# Orthrus_3_0_1-eagle_7_6.net
KiCad netlist of a schematic drawn in EAGLE
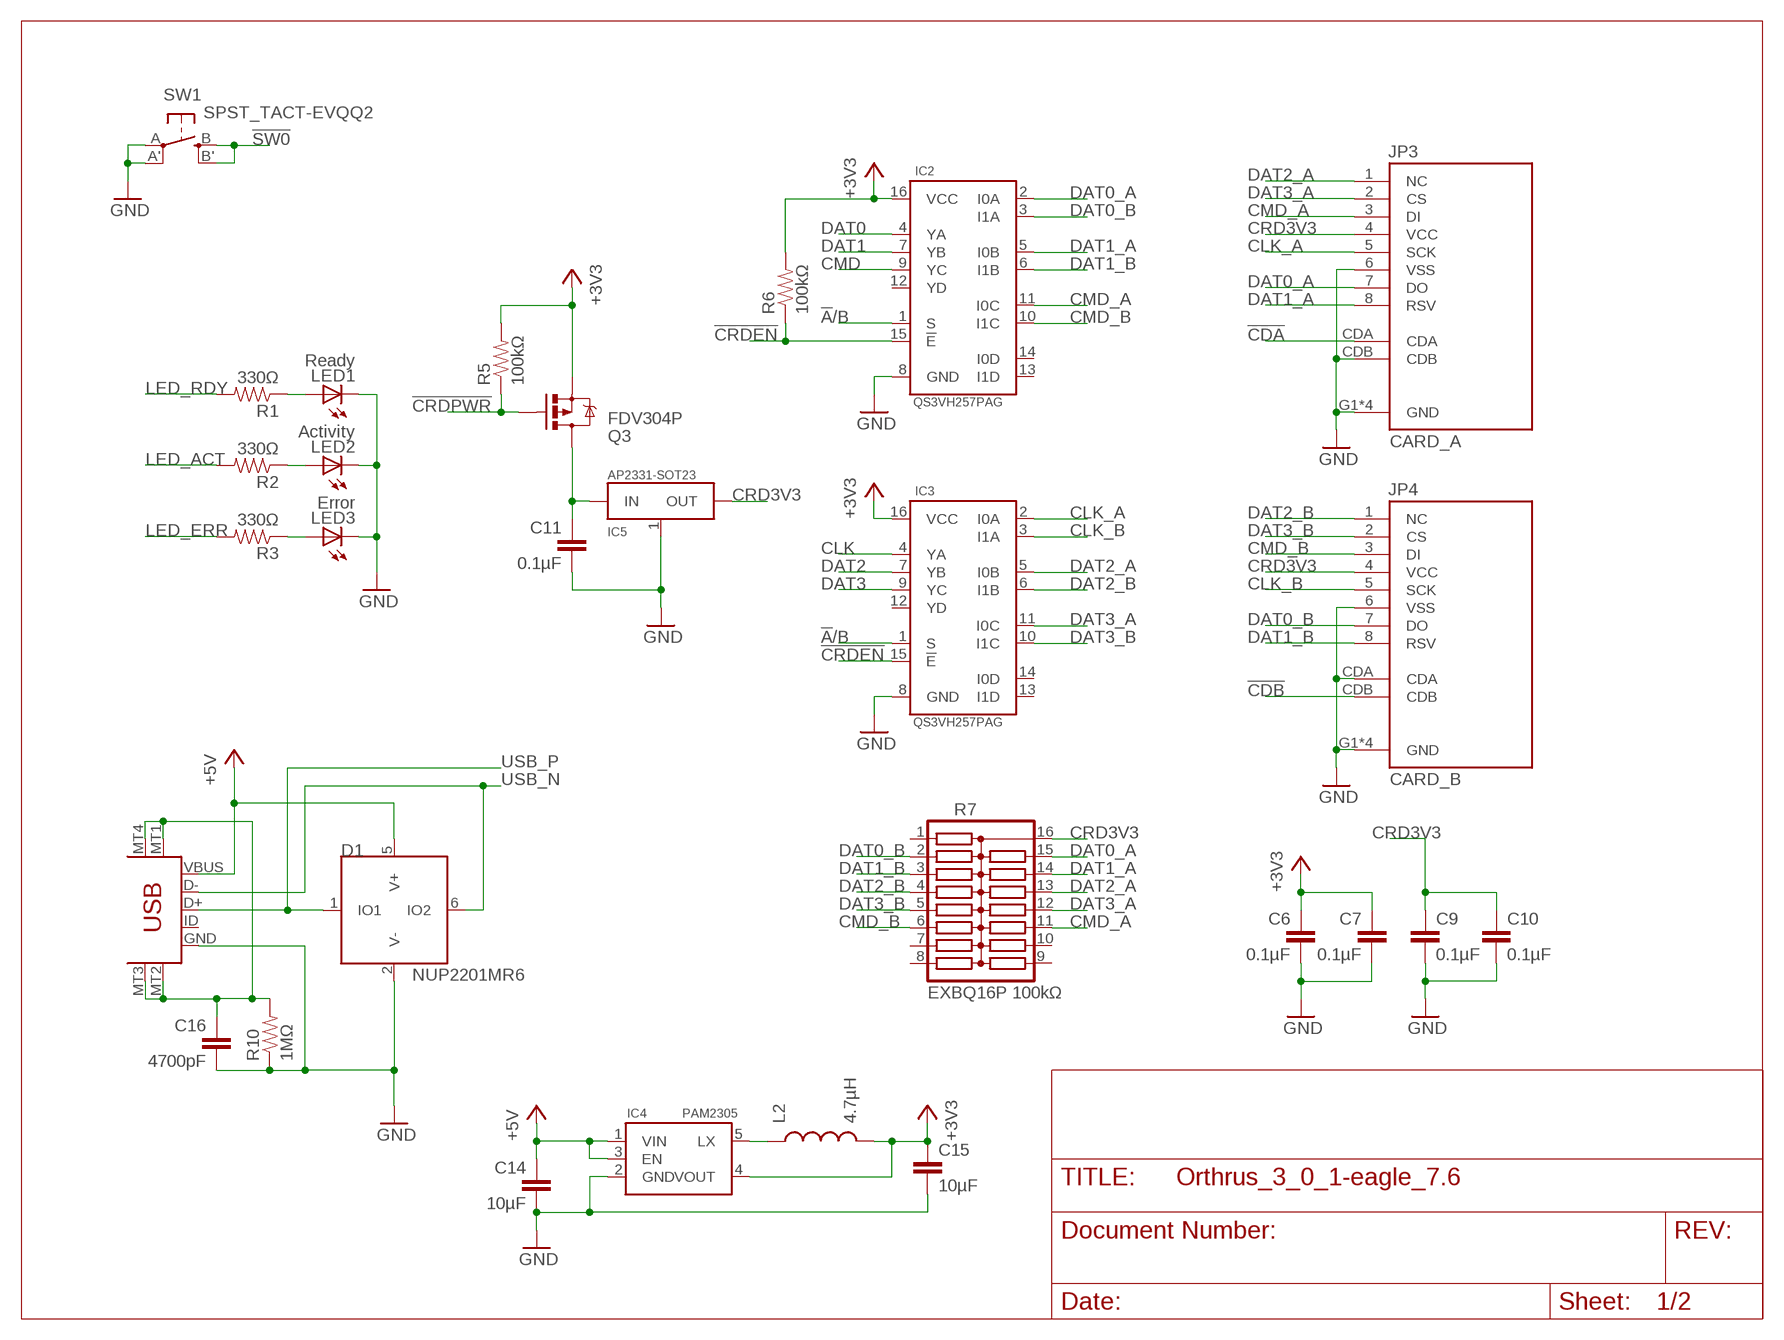
[diagram p0: schematic, sheet 1]
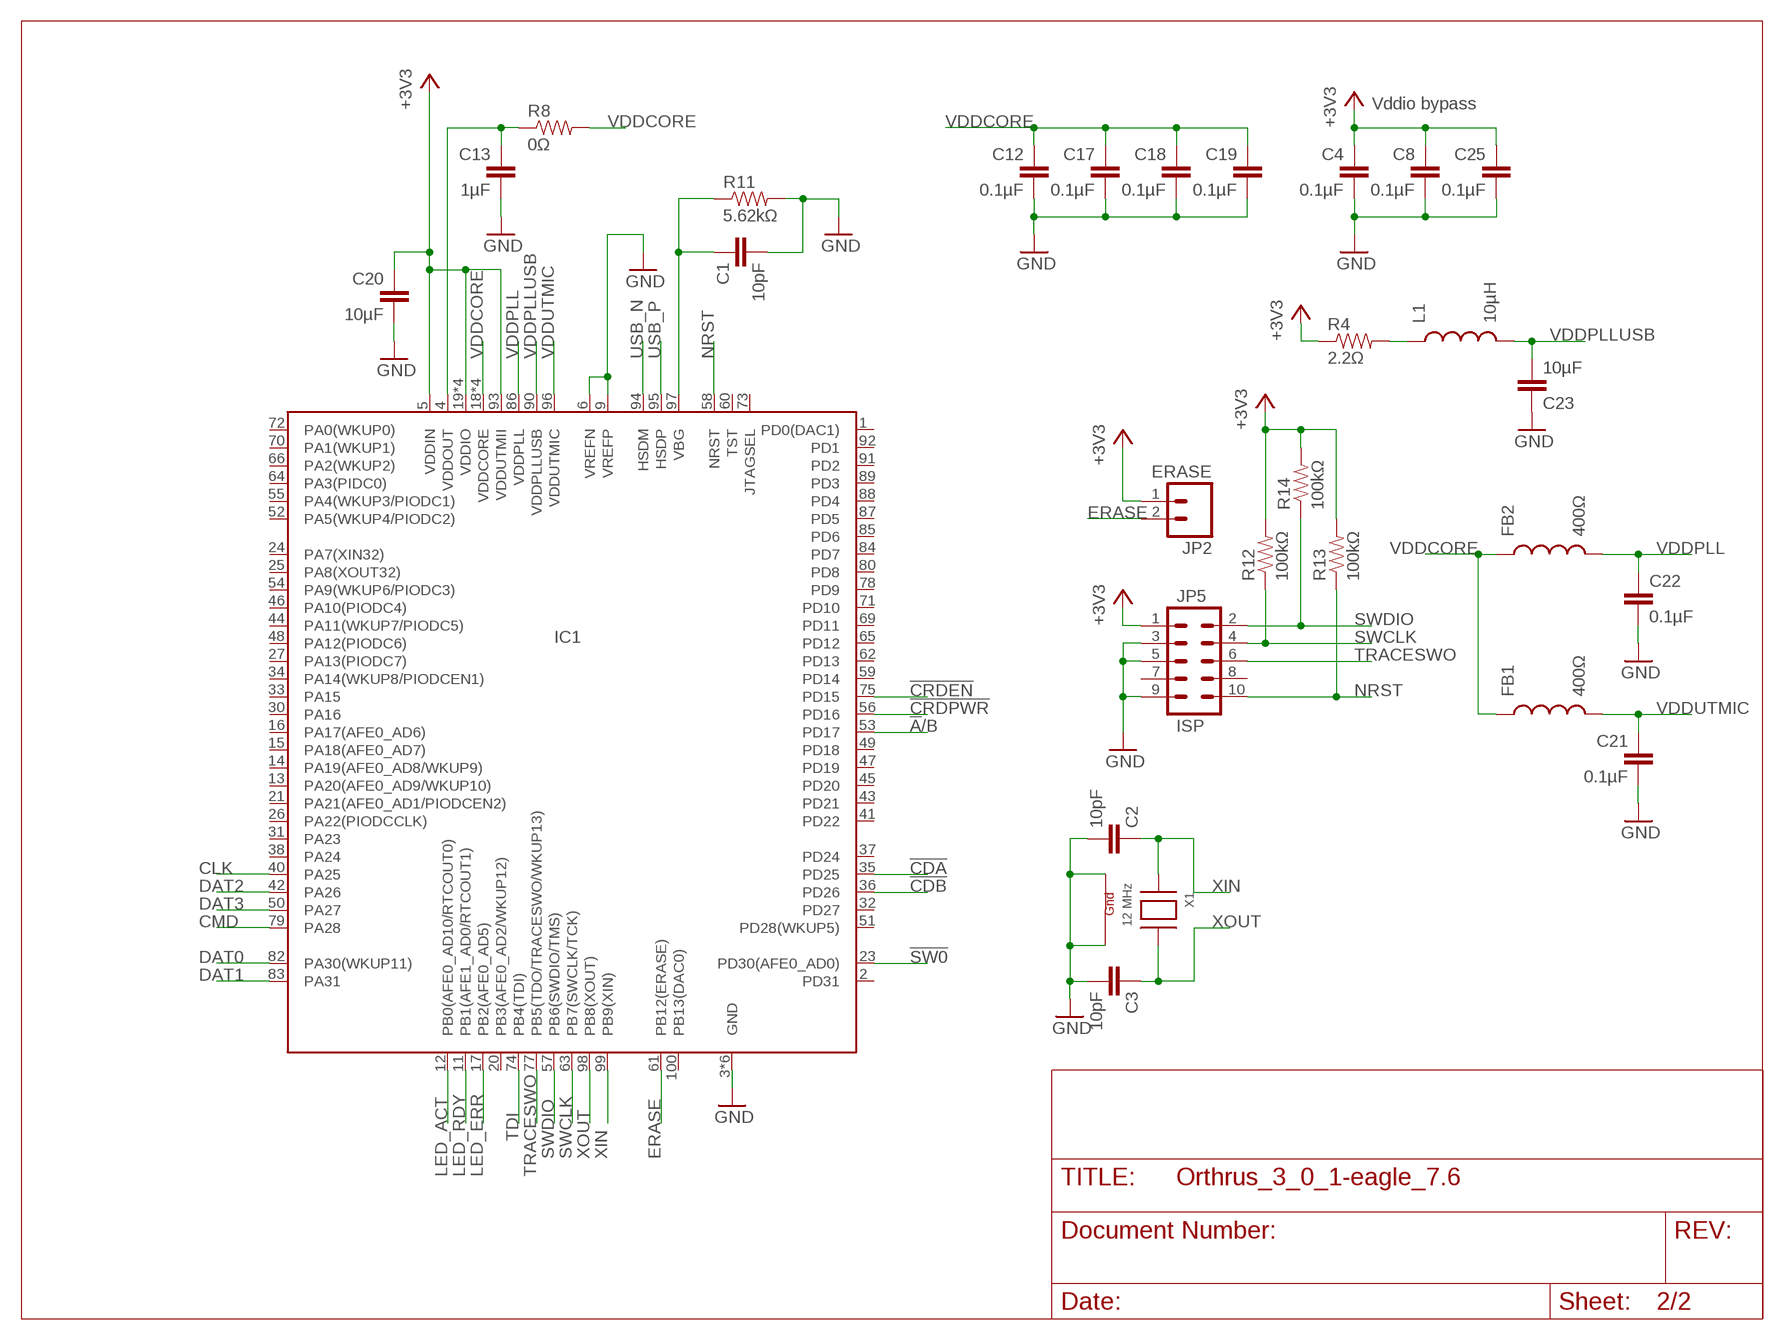
[diagram p1: schematic, sheet 2]

(export (version "E")
  (design (tool "Eeschema 10.0.6"))
  (components
    (comp (ref "C6")
      (value "0.1µF")
      (footprint "eagle-import:0805")
      (libsource (lib "eagle-import") (part "CAP0805"))
    )
    (comp (ref "C7")
      (value "0.1µF")
      (footprint "eagle-import:0805")
      (libsource (lib "eagle-import") (part "CAP0805"))
    )
    (comp (ref "C9")
      (value "0.1µF")
      (footprint "eagle-import:0805")
      (libsource (lib "eagle-import") (part "CAP0805"))
    )
    (comp (ref "C10")
      (value "0.1µF")
      (footprint "eagle-import:0805")
      (libsource (lib "eagle-import") (part "CAP0805"))
    )
    (comp (ref "C11")
      (value "0.1µF")
      (footprint "eagle-import:0805")
      (libsource (lib "eagle-import") (part "CAP0805"))
    )
    (comp (ref "C14")
      (value "10µF")
      (footprint "eagle-import:0805")
      (libsource (lib "eagle-import") (part "CAP0805"))
    )
    (comp (ref "C15")
      (value "10µF")
      (footprint "eagle-import:0805")
      (libsource (lib "eagle-import") (part "CAP0805"))
    )
    (comp (ref "C16")
      (value "4700pF")
      (footprint "eagle-import:0805")
      (libsource (lib "eagle-import") (part "CAP0805"))
    )
    (comp (ref "D1")
      (value "NUP2201MR6")
      (footprint "eagle-import:SOT23-6")
      (libsource (lib "eagle-import") (part "NUP2201MR6"))
    )
    (comp (ref "IC2")
      (value "QS3VH257PAG")
      (footprint "eagle-import:TSSOP16")
      (libsource (lib "eagle-import") (part "QS3VH257PAG"))
    )
    (comp (ref "IC3")
      (value "QS3VH257PAG")
      (footprint "eagle-import:TSSOP16")
      (libsource (lib "eagle-import") (part "QS3VH257PAG"))
    )
    (comp (ref "IC4")
      (value "PAM2305")
      (footprint "eagle-import:SOT23-5")
      (libsource (lib "eagle-import") (part "SC189XSKTRTSC189XSKTRT"))
    )
    (comp (ref "IC5")
      (value "AP2331-SOT23")
      (footprint "eagle-import:SOT23-3")
      (libsource (lib "eagle-import") (part "AP2331-SOT23"))
    )
    (comp (ref "JP1")
      (value "USB-5PIN-MICROB")
      (footprint "eagle-import:USB-MICROB")
      (libsource (lib "eagle-import") (part "USB-5PIN-MICROB"))
    )
    (comp (ref "JP3")
      (value "CARD_A")
      (footprint "eagle-import:DM3D-SF")
      (libsource (lib "eagle-import") (part "DM3D-SF"))
    )
    (comp (ref "JP4")
      (value "CARD_B")
      (footprint "eagle-import:DM3D-SF")
      (libsource (lib "eagle-import") (part "DM3D-SF"))
    )
    (comp (ref "L2")
      (value "4.7µH")
      (footprint "eagle-import:0805")
      (libsource (lib "eagle-import") (part "INDUCTOR0805"))
    )
    (comp (ref "LED1")
      (value "Ready")
      (footprint "eagle-import:CHIP-LED0805")
      (libsource (lib "eagle-import") (part "LEDCHIP-LED0805"))
    )
    (comp (ref "LED2")
      (value "Activity")
      (footprint "eagle-import:CHIP-LED0805")
      (libsource (lib "eagle-import") (part "LEDCHIP-LED0805"))
    )
    (comp (ref "LED3")
      (value "Error")
      (footprint "eagle-import:CHIP-LED0805")
      (libsource (lib "eagle-import") (part "LEDCHIP-LED0805"))
    )
    (comp (ref "Q3")
      (value "FDV304P")
      (footprint "eagle-import:SOT23-3")
      (libsource (lib "eagle-import") (part "MOSFET-PCHANNELSMD"))
    )
    (comp (ref "R1")
      (value "330Ω")
      (footprint "eagle-import:0805")
      (libsource (lib "eagle-import") (part "RESISTOR0805-RES"))
    )
    (comp (ref "R2")
      (value "330Ω")
      (footprint "eagle-import:0805")
      (libsource (lib "eagle-import") (part "RESISTOR0805-RES"))
    )
    (comp (ref "R3")
      (value "330Ω")
      (footprint "eagle-import:0805")
      (libsource (lib "eagle-import") (part "RESISTOR0805-RES"))
    )
    (comp (ref "R5")
      (value "100kΩ")
      (footprint "eagle-import:0805")
      (libsource (lib "eagle-import") (part "RESISTOR0805-RES"))
    )
    (comp (ref "R6")
      (value "100kΩ")
      (footprint "eagle-import:0805")
      (libsource (lib "eagle-import") (part "RESISTOR0805-RES"))
    )
    (comp (ref "R7")
      (value "EXBQ16P 100kΩ")
      (footprint "eagle-import:4816P")
      (fields (field (name "MF") "BOURNS, INC.") (field (name "MPN") "4816P-T02-824LF"))
      (libsource (lib "eagle-import") (part "4816P-T02"))
    )
    (comp (ref "R10")
      (value "1MΩ")
      (footprint "eagle-import:0805")
      (libsource (lib "eagle-import") (part "RESISTOR0805-RES"))
    )
    (comp (ref "SW1")
      (value "SPST_TACT-EVQQ2")
      (footprint "eagle-import:EVQ-Q2")
      (libsource (lib "eagle-import") (part "SPST_TACT-EVQQ2"))
    )
    (comp (ref "C1")
      (value "10pF")
      (footprint "eagle-import:0805")
      (libsource (lib "eagle-import") (part "CAP0805"))
    )
    (comp (ref "C2")
      (value "10pF")
      (footprint "eagle-import:0805")
      (libsource (lib "eagle-import") (part "CAP0805"))
    )
    (comp (ref "C3")
      (value "10pF")
      (footprint "eagle-import:0805")
      (libsource (lib "eagle-import") (part "CAP0805"))
    )
    (comp (ref "C4")
      (value "0.1µF")
      (footprint "eagle-import:0805")
      (libsource (lib "eagle-import") (part "CAP0805"))
    )
    (comp (ref "C8")
      (value "0.1µF")
      (footprint "eagle-import:0805")
      (libsource (lib "eagle-import") (part "CAP0805"))
    )
    (comp (ref "C12")
      (value "0.1µF")
      (footprint "eagle-import:0805")
      (libsource (lib "eagle-import") (part "CAP0805"))
    )
    (comp (ref "C13")
      (value "1µF")
      (footprint "eagle-import:0805")
      (libsource (lib "eagle-import") (part "CAP0805"))
    )
    (comp (ref "C17")
      (value "0.1µF")
      (footprint "eagle-import:0805")
      (libsource (lib "eagle-import") (part "CAP0805"))
    )
    (comp (ref "C18")
      (value "0.1µF")
      (footprint "eagle-import:0805")
      (libsource (lib "eagle-import") (part "CAP0805"))
    )
    (comp (ref "C19")
      (value "0.1µF")
      (footprint "eagle-import:0805")
      (libsource (lib "eagle-import") (part "CAP0805"))
    )
    (comp (ref "C20")
      (value "10µF")
      (footprint "eagle-import:0805")
      (libsource (lib "eagle-import") (part "CAP0805"))
    )
    (comp (ref "C21")
      (value "0.1µF")
      (footprint "eagle-import:0805")
      (libsource (lib "eagle-import") (part "CAP0805"))
    )
    (comp (ref "C22")
      (value "0.1µF")
      (footprint "eagle-import:0805")
      (libsource (lib "eagle-import") (part "CAP0805"))
    )
    (comp (ref "C23")
      (value "10µF")
      (footprint "eagle-import:0805")
      (libsource (lib "eagle-import") (part "CAP0805"))
    )
    (comp (ref "C25")
      (value "0.1µF")
      (footprint "eagle-import:0805")
      (libsource (lib "eagle-import") (part "CAP0805"))
    )
    (comp (ref "FB1")
      (value "400Ω")
      (footprint "eagle-import:0805")
      (libsource (lib "eagle-import") (part "INDUCTOR0805"))
    )
    (comp (ref "FB2")
      (value "400Ω")
      (footprint "eagle-import:0805")
      (libsource (lib "eagle-import") (part "INDUCTOR0805"))
    )
    (comp (ref "IC1")
      (value "ATSAMS70NXXAN")
      (footprint "eagle-import:TQFP100")
      (libsource (lib "eagle-import") (part "ATSAMS70NXXAN"))
    )
    (comp (ref "JP2")
      (value "ERASE")
      (footprint "eagle-import:1X02")
      (libsource (lib "eagle-import") (part "M02PTH"))
    )
    (comp (ref "JP5")
      (value "ISP")
      (footprint "eagle-import:JTAGICE3-50MIL")
      (libsource (lib "eagle-import") (part "M05X250MIL"))
    )
    (comp (ref "L1")
      (value "10µH")
      (footprint "eagle-import:0805")
      (libsource (lib "eagle-import") (part "INDUCTOR0805"))
    )
    (comp (ref "R4")
      (value "2.2Ω")
      (footprint "eagle-import:0805")
      (libsource (lib "eagle-import") (part "RESISTOR0805-RES"))
    )
    (comp (ref "R8")
      (value "0Ω")
      (footprint "eagle-import:0805-WITH-JUMPER")
      (libsource (lib "eagle-import") (part "RESISTOR0805-WITH-JUMPER"))
    )
    (comp (ref "R11")
      (value "5.62kΩ")
      (footprint "eagle-import:0805")
      (libsource (lib "eagle-import") (part "RESISTOR0805-RES"))
    )
    (comp (ref "R12")
      (value "100kΩ")
      (footprint "eagle-import:0805")
      (libsource (lib "eagle-import") (part "RESISTOR0805-RES"))
    )
    (comp (ref "R13")
      (value "100kΩ")
      (footprint "eagle-import:0805")
      (libsource (lib "eagle-import") (part "RESISTOR0805-RES"))
    )
    (comp (ref "R14")
      (value "100kΩ")
      (footprint "eagle-import:0805")
      (libsource (lib "eagle-import") (part "RESISTOR0805-RES"))
    )
    (comp (ref "X1")
      (value "12 MHz")
      (footprint "eagle-import:NX3225")
      (libsource (lib "eagle-import") (part "XTAL-4-3225"))
    )
  )
  (nets
    (net (code "1") (name "+3V3") (class "Default")
      (node (ref "C15") (pin "1") (pinfunction "1_1") (pintype "passive"))
      (node (ref "C20") (pin "1") (pinfunction "1_1") (pintype "passive"))
      (node (ref "C25") (pin "1") (pinfunction "1_1") (pintype "passive"))
      (node (ref "C4") (pin "1") (pinfunction "1_1") (pintype "passive"))
      (node (ref "C6") (pin "1") (pinfunction "1_1") (pintype "passive"))
      (node (ref "C7") (pin "1") (pinfunction "1_1") (pintype "passive"))
      (node (ref "C8") (pin "1") (pinfunction "1_1") (pintype "passive"))
      (node (ref "IC1") (pin "19") (pinfunction "VDDIO_19") (pintype "bidirectional"))
      (node (ref "IC1") (pin "28") (pinfunction "VDDIO_28") (pintype "bidirectional"))
      (node (ref "IC1") (pin "5") (pinfunction "VDDIN_5") (pintype "bidirectional"))
      (node (ref "IC1") (pin "68") (pinfunction "VDDIO_68") (pintype "bidirectional"))
      (node (ref "IC1") (pin "81") (pinfunction "VDDIO_81") (pintype "bidirectional"))
      (node (ref "IC1") (pin "93") (pinfunction "VDDUTMII_93") (pintype "bidirectional"))
      (node (ref "IC2") (pin "16") (pinfunction "VCC_16") (pintype "power_in"))
      (node (ref "IC3") (pin "16") (pinfunction "VCC_16") (pintype "power_in"))
      (node (ref "IC4") (pin "4") (pinfunction "VOUT_4") (pintype "bidirectional"))
      (node (ref "JP2") (pin "1") (pinfunction "1_1") (pintype "passive"))
      (node (ref "JP5") (pin "1") (pinfunction "1_1") (pintype "passive"))
      (node (ref "L2") (pin "2") (pinfunction "2_2") (pintype "passive"))
      (node (ref "Q3") (pin "2") (pinfunction "S_2") (pintype "passive"))
      (node (ref "R12") (pin "2") (pinfunction "2_2") (pintype "passive"))
      (node (ref "R13") (pin "2") (pinfunction "2_2") (pintype "passive"))
      (node (ref "R14") (pin "2") (pinfunction "2_2") (pintype "passive"))
      (node (ref "R4") (pin "1") (pinfunction "1_1") (pintype "passive"))
      (node (ref "R5") (pin "2") (pinfunction "2_2") (pintype "passive"))
      (node (ref "R6") (pin "2") (pinfunction "2_2") (pintype "passive"))
    )
    (net (code "2") (name "+5V") (class "Default")
      (node (ref "C14") (pin "1") (pinfunction "1_1") (pintype "passive"))
      (node (ref "D1") (pin "5") (pinfunction "V+_5") (pintype "bidirectional"))
      (node (ref "IC4") (pin "1") (pinfunction "VIN_1") (pintype "bidirectional"))
      (node (ref "IC4") (pin "3") (pinfunction "EN_3") (pintype "bidirectional"))
      (node (ref "JP1") (pin "VBUS") (pinfunction "VBUS_VBUS") (pintype "bidirectional"))
    )
    (net (code "3") (name "CLK") (class "Default")
      (node (ref "IC1") (pin "40") (pinfunction "PA25_40") (pintype "bidirectional"))
      (node (ref "IC3") (pin "4") (pinfunction "YA_4") (pintype "bidirectional"))
    )
    (net (code "4") (name "CLK_A") (class "Default")
      (node (ref "IC3") (pin "2") (pinfunction "I0A_2") (pintype "bidirectional"))
      (node (ref "JP3") (pin "5") (pinfunction "SCK_5") (pintype "bidirectional"))
    )
    (net (code "5") (name "CLK_B") (class "Default")
      (node (ref "IC3") (pin "3") (pinfunction "I1A_3") (pintype "bidirectional"))
      (node (ref "JP4") (pin "5") (pinfunction "SCK_5") (pintype "bidirectional"))
    )
    (net (code "6") (name "CMD") (class "Default")
      (node (ref "IC1") (pin "79") (pinfunction "PA28_79") (pintype "bidirectional"))
      (node (ref "IC2") (pin "9") (pinfunction "YC_9") (pintype "bidirectional"))
    )
    (net (code "7") (name "CMD_A") (class "Default")
      (node (ref "IC2") (pin "11") (pinfunction "I0C_11") (pintype "bidirectional"))
      (node (ref "JP3") (pin "3") (pinfunction "DI_3") (pintype "bidirectional"))
      (node (ref "R7") (pin "11") (pinfunction "11_11") (pintype "passive"))
    )
    (net (code "8") (name "CMD_B") (class "Default")
      (node (ref "IC2") (pin "10") (pinfunction "I1C_10") (pintype "bidirectional"))
      (node (ref "JP4") (pin "3") (pinfunction "DI_3") (pintype "bidirectional"))
      (node (ref "R7") (pin "6") (pinfunction "6_6") (pintype "passive"))
    )
    (net (code "9") (name "CRD3V3") (class "Default")
      (node (ref "C10") (pin "1") (pinfunction "1_1") (pintype "passive"))
      (node (ref "C9") (pin "1") (pinfunction "1_1") (pintype "passive"))
      (node (ref "IC5") (pin "2") (pinfunction "OUT_2") (pintype "output"))
      (node (ref "JP3") (pin "4") (pinfunction "VCC_4") (pintype "bidirectional"))
      (node (ref "JP4") (pin "4") (pinfunction "VCC_4") (pintype "bidirectional"))
      (node (ref "R7") (pin "16") (pinfunction "16_16") (pintype "passive"))
    )
    (net (code "10") (name "DAT0") (class "Default")
      (node (ref "IC1") (pin "82") (pinfunction "PA30(WKUP11)_82") (pintype "bidirectional"))
      (node (ref "IC2") (pin "4") (pinfunction "YA_4") (pintype "bidirectional"))
    )
    (net (code "11") (name "DAT0_A") (class "Default")
      (node (ref "IC2") (pin "2") (pinfunction "I0A_2") (pintype "bidirectional"))
      (node (ref "JP3") (pin "7") (pinfunction "DO_7") (pintype "bidirectional"))
      (node (ref "R7") (pin "15") (pinfunction "15_15") (pintype "passive"))
    )
    (net (code "12") (name "DAT0_B") (class "Default")
      (node (ref "IC2") (pin "3") (pinfunction "I1A_3") (pintype "bidirectional"))
      (node (ref "JP4") (pin "7") (pinfunction "DO_7") (pintype "bidirectional"))
      (node (ref "R7") (pin "2") (pinfunction "2_2") (pintype "passive"))
    )
    (net (code "13") (name "DAT1") (class "Default")
      (node (ref "IC1") (pin "83") (pinfunction "PA31_83") (pintype "bidirectional"))
      (node (ref "IC2") (pin "7") (pinfunction "YB_7") (pintype "bidirectional"))
    )
    (net (code "14") (name "DAT1_A") (class "Default")
      (node (ref "IC2") (pin "5") (pinfunction "I0B_5") (pintype "bidirectional"))
      (node (ref "JP3") (pin "8") (pinfunction "RSV_8") (pintype "bidirectional"))
      (node (ref "R7") (pin "14") (pinfunction "14_14") (pintype "passive"))
    )
    (net (code "15") (name "DAT1_B") (class "Default")
      (node (ref "IC2") (pin "6") (pinfunction "I1B_6") (pintype "bidirectional"))
      (node (ref "JP4") (pin "8") (pinfunction "RSV_8") (pintype "bidirectional"))
      (node (ref "R7") (pin "3") (pinfunction "3_3") (pintype "passive"))
    )
    (net (code "16") (name "DAT2") (class "Default")
      (node (ref "IC1") (pin "42") (pinfunction "PA26_42") (pintype "bidirectional"))
      (node (ref "IC3") (pin "7") (pinfunction "YB_7") (pintype "bidirectional"))
    )
    (net (code "17") (name "DAT2_A") (class "Default")
      (node (ref "IC3") (pin "5") (pinfunction "I0B_5") (pintype "bidirectional"))
      (node (ref "JP3") (pin "1") (pinfunction "NC_1") (pintype "bidirectional"))
      (node (ref "R7") (pin "13") (pinfunction "13_13") (pintype "passive"))
    )
    (net (code "18") (name "DAT2_B") (class "Default")
      (node (ref "IC3") (pin "6") (pinfunction "I1B_6") (pintype "bidirectional"))
      (node (ref "JP4") (pin "1") (pinfunction "NC_1") (pintype "bidirectional"))
      (node (ref "R7") (pin "4") (pinfunction "4_4") (pintype "passive"))
    )
    (net (code "19") (name "DAT3") (class "Default")
      (node (ref "IC1") (pin "50") (pinfunction "PA27_50") (pintype "bidirectional"))
      (node (ref "IC3") (pin "9") (pinfunction "YC_9") (pintype "bidirectional"))
    )
    (net (code "20") (name "DAT3_A") (class "Default")
      (node (ref "IC3") (pin "11") (pinfunction "I0C_11") (pintype "bidirectional"))
      (node (ref "JP3") (pin "2") (pinfunction "CS_2") (pintype "bidirectional"))
      (node (ref "R7") (pin "12") (pinfunction "12_12") (pintype "passive"))
    )
    (net (code "21") (name "DAT3_B") (class "Default")
      (node (ref "IC3") (pin "10") (pinfunction "I1C_10") (pintype "bidirectional"))
      (node (ref "JP4") (pin "2") (pinfunction "CS_2") (pintype "bidirectional"))
      (node (ref "R7") (pin "5") (pinfunction "5_5") (pintype "passive"))
    )
    (net (code "22") (name "ERASE") (class "Default")
      (node (ref "IC1") (pin "61") (pinfunction "PB12(ERASE)_61") (pintype "bidirectional"))
      (node (ref "JP2") (pin "2") (pinfunction "2_2") (pintype "passive"))
    )
    (net (code "23") (name "GND") (class "Default")
      (node (ref "C1") (pin "2") (pinfunction "2_2") (pintype "passive"))
      (node (ref "C10") (pin "2") (pinfunction "2_2") (pintype "passive"))
      (node (ref "C11") (pin "2") (pinfunction "2_2") (pintype "passive"))
      (node (ref "C12") (pin "2") (pinfunction "2_2") (pintype "passive"))
      (node (ref "C13") (pin "2") (pinfunction "2_2") (pintype "passive"))
      (node (ref "C14") (pin "2") (pinfunction "2_2") (pintype "passive"))
      (node (ref "C15") (pin "2") (pinfunction "2_2") (pintype "passive"))
      (node (ref "C16") (pin "2") (pinfunction "2_2") (pintype "passive"))
      (node (ref "C17") (pin "2") (pinfunction "2_2") (pintype "passive"))
      (node (ref "C18") (pin "2") (pinfunction "2_2") (pintype "passive"))
      (node (ref "C19") (pin "2") (pinfunction "2_2") (pintype "passive"))
      (node (ref "C2") (pin "2") (pinfunction "2_2") (pintype "passive"))
      (node (ref "C20") (pin "2") (pinfunction "2_2") (pintype "passive"))
      (node (ref "C21") (pin "2") (pinfunction "2_2") (pintype "passive"))
      (node (ref "C22") (pin "2") (pinfunction "2_2") (pintype "passive"))
      (node (ref "C23") (pin "1") (pinfunction "1_1") (pintype "passive"))
      (node (ref "C25") (pin "2") (pinfunction "2_2") (pintype "passive"))
      (node (ref "C3") (pin "2") (pinfunction "2_2") (pintype "passive"))
      (node (ref "C4") (pin "2") (pinfunction "2_2") (pintype "passive"))
      (node (ref "C6") (pin "2") (pinfunction "2_2") (pintype "passive"))
      (node (ref "C7") (pin "2") (pinfunction "2_2") (pintype "passive"))
      (node (ref "C8") (pin "2") (pinfunction "2_2") (pintype "passive"))
      (node (ref "C9") (pin "2") (pinfunction "2_2") (pintype "passive"))
      (node (ref "D1") (pin "2") (pinfunction "V-_2") (pintype "bidirectional"))
      (node (ref "IC1") (pin "10") (pinfunction "GND_10") (pintype "bidirectional"))
      (node (ref "IC1") (pin "29") (pinfunction "GND_29") (pintype "bidirectional"))
      (node (ref "IC1") (pin "3") (pinfunction "GND_3") (pintype "bidirectional"))
      (node (ref "IC1") (pin "6") (pinfunction "VREFN_6") (pintype "bidirectional"))
      (node (ref "IC1") (pin "67") (pinfunction "GND_67") (pintype "bidirectional"))
      (node (ref "IC1") (pin "7") (pinfunction "GND_7") (pintype "bidirectional"))
      (node (ref "IC1") (pin "8") (pinfunction "GND_8") (pintype "bidirectional"))
      (node (ref "IC1") (pin "9") (pinfunction "VREFP_9") (pintype "bidirectional"))
      (node (ref "IC2") (pin "8") (pinfunction "GND_8") (pintype "power_in"))
      (node (ref "IC3") (pin "8") (pinfunction "GND_8") (pintype "power_in"))
      (node (ref "IC4") (pin "2") (pinfunction "GND_2") (pintype "bidirectional"))
      (node (ref "IC5") (pin "1") (pinfunction "GND_1") (pintype "power_in"))
      (node (ref "JP1") (pin "GND") (pinfunction "GND_GND") (pintype "bidirectional"))
      (node (ref "JP3") (pin "6") (pinfunction "VSS_6") (pintype "bidirectional"))
      (node (ref "JP3") (pin "CDB") (pinfunction "CDB_CDB") (pintype "bidirectional"))
      (node (ref "JP3") (pin "G1") (pinfunction "GND_G1") (pintype "bidirectional"))
      (node (ref "JP3") (pin "G2") (pinfunction "GND_G2") (pintype "bidirectional"))
      (node (ref "JP3") (pin "G3") (pinfunction "GND_G3") (pintype "bidirectional"))
      (node (ref "JP3") (pin "G4") (pinfunction "GND_G4") (pintype "bidirectional"))
      (node (ref "JP4") (pin "6") (pinfunction "VSS_6") (pintype "bidirectional"))
      (node (ref "JP4") (pin "CDA") (pinfunction "CDA_CDA") (pintype "bidirectional"))
      (node (ref "JP4") (pin "G1") (pinfunction "GND_G1") (pintype "bidirectional"))
      (node (ref "JP4") (pin "G2") (pinfunction "GND_G2") (pintype "bidirectional"))
      (node (ref "JP4") (pin "G3") (pinfunction "GND_G3") (pintype "bidirectional"))
      (node (ref "JP4") (pin "G4") (pinfunction "GND_G4") (pintype "bidirectional"))
      (node (ref "JP5") (pin "3") (pinfunction "3_3") (pintype "passive"))
      (node (ref "JP5") (pin "5") (pinfunction "5_5") (pintype "passive"))
      (node (ref "JP5") (pin "9") (pinfunction "9_9") (pintype "passive"))
      (node (ref "LED1") (pin "C") (pinfunction "C_C") (pintype "passive"))
      (node (ref "LED2") (pin "C") (pinfunction "C_C") (pintype "passive"))
      (node (ref "LED3") (pin "C") (pinfunction "C_C") (pintype "passive"))
      (node (ref "R10") (pin "1") (pinfunction "1_1") (pintype "passive"))
      (node (ref "R11") (pin "2") (pinfunction "2_2") (pintype "passive"))
      (node (ref "SW1") (pin "A") (pinfunction "P_A") (pintype "passive"))
      (node (ref "SW1") (pin "A'") (pinfunction "P1_A'") (pintype "passive"))
      (node (ref "X1") (pin "2") (pinfunction "G2_2") (pintype "passive"))
      (node (ref "X1") (pin "4") (pinfunction "G1_4") (pintype "passive"))
    )
    (net (code "24") (name "LED_ACT") (class "Default")
      (node (ref "IC1") (pin "12") (pinfunction "PB0(AFE0_AD10/RTCOUT0)_12") (pintype "bidirectional"))
      (node (ref "R2") (pin "2") (pinfunction "2_2") (pintype "passive"))
    )
    (net (code "25") (name "LED_ERR") (class "Default")
      (node (ref "IC1") (pin "17") (pinfunction "PB2(AFE0_AD5)_17") (pintype "bidirectional"))
      (node (ref "R3") (pin "2") (pinfunction "2_2") (pintype "passive"))
    )
    (net (code "26") (name "LED_RDY") (class "Default")
      (node (ref "IC1") (pin "11") (pinfunction "PB1(AFE1_AD0/RTCOUT1)_11") (pintype "bidirectional"))
      (node (ref "R1") (pin "2") (pinfunction "2_2") (pintype "passive"))
    )
    (net (code "27") (name "NRST") (class "Default")
      (node (ref "IC1") (pin "58") (pinfunction "NRST_58") (pintype "bidirectional"))
      (node (ref "JP5") (pin "10") (pinfunction "10_10") (pintype "passive"))
      (node (ref "R13") (pin "1") (pinfunction "1_1") (pintype "passive"))
    )
    (net (code "28") (name "Net-(IC1-VBG)") (class "Default")
      (node (ref "C1") (pin "1") (pinfunction "1_1") (pintype "passive"))
      (node (ref "IC1") (pin "97") (pinfunction "VBG_97") (pintype "bidirectional"))
      (node (ref "R11") (pin "1") (pinfunction "1_1") (pintype "passive"))
    )
    (net (code "29") (name "Net-(IC1-VDDOUT)") (class "Default")
      (node (ref "C13") (pin "1") (pinfunction "1_1") (pintype "passive"))
      (node (ref "IC1") (pin "4") (pinfunction "VDDOUT_4") (pintype "bidirectional"))
      (node (ref "R8") (pin "1") (pinfunction "1_1") (pintype "passive"))
    )
    (net (code "30") (name "Net-(IC4-LX)") (class "Default")
      (node (ref "IC4") (pin "5") (pinfunction "LX_5") (pintype "bidirectional"))
      (node (ref "L2") (pin "1") (pinfunction "1_1") (pintype "passive"))
    )
    (net (code "31") (name "Net-(IC5-IN)") (class "Default")
      (node (ref "C11") (pin "1") (pinfunction "1_1") (pintype "passive"))
      (node (ref "IC5") (pin "3") (pinfunction "IN_3") (pintype "power_in"))
      (node (ref "Q3") (pin "3") (pinfunction "D_3") (pintype "passive"))
    )
    (net (code "32") (name "Net-(JP1-MTN1)") (class "Default")
      (node (ref "C16") (pin "1") (pinfunction "1_1") (pintype "passive"))
      (node (ref "JP1") (pin "MT1") (pinfunction "MTN1_MT1") (pintype "bidirectional"))
      (node (ref "JP1") (pin "MT2") (pinfunction "MTN3_MT2") (pintype "bidirectional"))
      (node (ref "JP1") (pin "MT3") (pinfunction "MTN4_MT3") (pintype "bidirectional"))
      (node (ref "JP1") (pin "MT4") (pinfunction "MTN2_MT4") (pintype "bidirectional"))
      (node (ref "R10") (pin "2") (pinfunction "2_2") (pintype "passive"))
    )
    (net (code "33") (name "Net-(L1-Pad1)") (class "Default")
      (node (ref "L1") (pin "1") (pinfunction "1_1") (pintype "passive"))
      (node (ref "R4") (pin "2") (pinfunction "2_2") (pintype "passive"))
    )
    (net (code "34") (name "Net-(LED1-PadA)") (class "Default")
      (node (ref "LED1") (pin "A") (pinfunction "A_A") (pintype "passive"))
      (node (ref "R1") (pin "1") (pinfunction "1_1") (pintype "passive"))
    )
    (net (code "35") (name "Net-(LED2-PadA)") (class "Default")
      (node (ref "LED2") (pin "A") (pinfunction "A_A") (pintype "passive"))
      (node (ref "R2") (pin "1") (pinfunction "1_1") (pintype "passive"))
    )
    (net (code "36") (name "Net-(LED3-PadA)") (class "Default")
      (node (ref "LED3") (pin "A") (pinfunction "A_A") (pintype "passive"))
      (node (ref "R3") (pin "1") (pinfunction "1_1") (pintype "passive"))
    )
    (net (code "37") (name "SWCLK") (class "Default")
      (node (ref "IC1") (pin "63") (pinfunction "PB7(SWCLK/TCK)_63") (pintype "bidirectional"))
      (node (ref "JP5") (pin "4") (pinfunction "4_4") (pintype "passive"))
      (node (ref "R12") (pin "1") (pinfunction "1_1") (pintype "passive"))
    )
    (net (code "38") (name "SWDIO") (class "Default")
      (node (ref "IC1") (pin "57") (pinfunction "PB6(SWDIO/TMS)_57") (pintype "bidirectional"))
      (node (ref "JP5") (pin "2") (pinfunction "2_2") (pintype "passive"))
      (node (ref "R14") (pin "1") (pinfunction "1_1") (pintype "passive"))
    )
    (net (code "39") (name "TDI") (class "Default")
      (node (ref "IC1") (pin "74") (pinfunction "PB4(TDI)_74") (pintype "bidirectional"))
    )
    (net (code "40") (name "TRACESWO") (class "Default")
      (node (ref "IC1") (pin "77") (pinfunction "PB5(TDO/TRACESWO/WKUP13)_77") (pintype "bidirectional"))
      (node (ref "JP5") (pin "6") (pinfunction "6_6") (pintype "passive"))
    )
    (net (code "41") (name "USB_N") (class "Default")
      (node (ref "D1") (pin "6") (pinfunction "IO2_6") (pintype "bidirectional"))
      (node (ref "IC1") (pin "94") (pinfunction "HSDM_94") (pintype "bidirectional"))
      (node (ref "JP1") (pin "D-") (pinfunction "D-_D-") (pintype "bidirectional"))
    )
    (net (code "42") (name "USB_P") (class "Default")
      (node (ref "D1") (pin "1") (pinfunction "IO1_1") (pintype "bidirectional"))
      (node (ref "IC1") (pin "95") (pinfunction "HSDP_95") (pintype "bidirectional"))
      (node (ref "JP1") (pin "D+") (pinfunction "D+_D+") (pintype "bidirectional"))
    )
    (net (code "43") (name "VDDCORE") (class "Default")
      (node (ref "C12") (pin "1") (pinfunction "1_1") (pintype "passive"))
      (node (ref "C17") (pin "1") (pinfunction "1_1") (pintype "passive"))
      (node (ref "C18") (pin "1") (pinfunction "1_1") (pintype "passive"))
      (node (ref "C19") (pin "1") (pinfunction "1_1") (pintype "passive"))
      (node (ref "FB1") (pin "1") (pinfunction "1_1") (pintype "passive"))
      (node (ref "FB2") (pin "1") (pinfunction "1_1") (pintype "passive"))
      (node (ref "IC1") (pin "18") (pinfunction "VDDCORE_18") (pintype "bidirectional"))
      (node (ref "IC1") (pin "22") (pinfunction "VDDCORE_22") (pintype "bidirectional"))
      (node (ref "IC1") (pin "39") (pinfunction "VDDCORE_39") (pintype "bidirectional"))
      (node (ref "IC1") (pin "76") (pinfunction "VDDCORE_76") (pintype "bidirectional"))
      (node (ref "R8") (pin "2") (pinfunction "2_2") (pintype "passive"))
    )
    (net (code "44") (name "VDDPLL") (class "Default")
      (node (ref "C22") (pin "1") (pinfunction "1_1") (pintype "passive"))
      (node (ref "FB2") (pin "2") (pinfunction "2_2") (pintype "passive"))
      (node (ref "IC1") (pin "86") (pinfunction "VDDPLL_86") (pintype "bidirectional"))
    )
    (net (code "45") (name "VDDPLLUSB") (class "Default")
      (node (ref "C23") (pin "2") (pinfunction "2_2") (pintype "passive"))
      (node (ref "IC1") (pin "90") (pinfunction "VDDPLLUSB_90") (pintype "bidirectional"))
      (node (ref "L1") (pin "2") (pinfunction "2_2") (pintype "passive"))
    )
    (net (code "46") (name "VDDUTMIC") (class "Default")
      (node (ref "C21") (pin "1") (pinfunction "1_1") (pintype "passive"))
      (node (ref "FB1") (pin "2") (pinfunction "2_2") (pintype "passive"))
      (node (ref "IC1") (pin "96") (pinfunction "VDDUTMIC_96") (pintype "bidirectional"))
    )
    (net (code "47") (name "XIN") (class "Default")
      (node (ref "C2") (pin "1") (pinfunction "1_1") (pintype "passive"))
      (node (ref "IC1") (pin "99") (pinfunction "PB9(XIN)_99") (pintype "bidirectional"))
      (node (ref "X1") (pin "1") (pinfunction "X1_1") (pintype "bidirectional"))
    )
    (net (code "48") (name "XOUT") (class "Default")
      (node (ref "C3") (pin "1") (pinfunction "1_1") (pintype "passive"))
      (node (ref "IC1") (pin "98") (pinfunction "PB8(XOUT)_98") (pintype "bidirectional"))
      (node (ref "X1") (pin "3") (pinfunction "X2_3") (pintype "bidirectional"))
    )
    (net (code "49") (name "unconnected-(IC1-JTAGSEL-Pad73)") (class "Default")
      (node (ref "IC1") (pin "73") (pinfunction "JTAGSEL_73") (pintype "bidirectional"))
    )
    (net (code "50") (name "unconnected-(IC1-PA0(WKUP0)-Pad72)") (class "Default")
      (node (ref "IC1") (pin "72") (pinfunction "PA0(WKUP0)_72") (pintype "bidirectional"))
    )
    (net (code "51") (name "unconnected-(IC1-PA1(WKUP1)-Pad70)") (class "Default")
      (node (ref "IC1") (pin "70") (pinfunction "PA1(WKUP1)_70") (pintype "bidirectional"))
    )
    (net (code "52") (name "unconnected-(IC1-PA2(WKUP2)-Pad66)") (class "Default")
      (node (ref "IC1") (pin "66") (pinfunction "PA2(WKUP2)_66") (pintype "bidirectional"))
    )
    (net (code "53") (name "unconnected-(IC1-PA3(PIDC0)-Pad64)") (class "Default")
      (node (ref "IC1") (pin "64") (pinfunction "PA3(PIDC0)_64") (pintype "bidirectional"))
    )
    (net (code "54") (name "unconnected-(IC1-PA4(WKUP3{slash}PIODC1)-Pad55)") (class "Default")
      (node (ref "IC1") (pin "55") (pinfunction "PA4(WKUP3/PIODC1)_55") (pintype "bidirectional"))
    )
    (net (code "55") (name "unconnected-(IC1-PA5(WKUP4{slash}PIODC2)-Pad52)") (class "Default")
      (node (ref "IC1") (pin "52") (pinfunction "PA5(WKUP4/PIODC2)_52") (pintype "bidirectional"))
    )
    (net (code "56") (name "unconnected-(IC1-PA7(XIN32)-Pad24)") (class "Default")
      (node (ref "IC1") (pin "24") (pinfunction "PA7(XIN32)_24") (pintype "bidirectional"))
    )
    (net (code "57") (name "unconnected-(IC1-PA8(XOUT32)-Pad25)") (class "Default")
      (node (ref "IC1") (pin "25") (pinfunction "PA8(XOUT32)_25") (pintype "bidirectional"))
    )
    (net (code "58") (name "unconnected-(IC1-PA9(WKUP6{slash}PIODC3)-Pad54)") (class "Default")
      (node (ref "IC1") (pin "54") (pinfunction "PA9(WKUP6/PIODC3)_54") (pintype "bidirectional"))
    )
    (net (code "59") (name "unconnected-(IC1-PA10(PIODC4)-Pad46)") (class "Default")
      (node (ref "IC1") (pin "46") (pinfunction "PA10(PIODC4)_46") (pintype "bidirectional"))
    )
    (net (code "60") (name "unconnected-(IC1-PA11(WKUP7{slash}PIODC5)-Pad44)") (class "Default")
      (node (ref "IC1") (pin "44") (pinfunction "PA11(WKUP7/PIODC5)_44") (pintype "bidirectional"))
    )
    (net (code "61") (name "unconnected-(IC1-PA12(PIODC6)-Pad48)") (class "Default")
      (node (ref "IC1") (pin "48") (pinfunction "PA12(PIODC6)_48") (pintype "bidirectional"))
    )
    (net (code "62") (name "unconnected-(IC1-PA13(PIODC7)-Pad27)") (class "Default")
      (node (ref "IC1") (pin "27") (pinfunction "PA13(PIODC7)_27") (pintype "bidirectional"))
    )
    (net (code "63") (name "unconnected-(IC1-PA14(WKUP8{slash}PIODCEN1)-Pad34)") (class "Default")
      (node (ref "IC1") (pin "34") (pinfunction "PA14(WKUP8/PIODCEN1)_34") (pintype "bidirectional"))
    )
    (net (code "64") (name "unconnected-(IC1-PA15-Pad33)") (class "Default")
      (node (ref "IC1") (pin "33") (pinfunction "PA15_33") (pintype "bidirectional"))
    )
    (net (code "65") (name "unconnected-(IC1-PA16-Pad30)") (class "Default")
      (node (ref "IC1") (pin "30") (pinfunction "PA16_30") (pintype "bidirectional"))
    )
    (net (code "66") (name "unconnected-(IC1-PA17(AFE0_AD6)-Pad16)") (class "Default")
      (node (ref "IC1") (pin "16") (pinfunction "PA17(AFE0_AD6)_16") (pintype "bidirectional"))
    )
    (net (code "67") (name "unconnected-(IC1-PA18(AFE0_AD7)-Pad15)") (class "Default")
      (node (ref "IC1") (pin "15") (pinfunction "PA18(AFE0_AD7)_15") (pintype "bidirectional"))
    )
    (net (code "68") (name "unconnected-(IC1-PA19(AFE0_AD8{slash}WKUP9)-Pad14)") (class "Default")
      (node (ref "IC1") (pin "14") (pinfunction "PA19(AFE0_AD8/WKUP9)_14") (pintype "bidirectional"))
    )
    (net (code "69") (name "unconnected-(IC1-PA20(AFE0_AD9{slash}WKUP10)-Pad13)") (class "Default")
      (node (ref "IC1") (pin "13") (pinfunction "PA20(AFE0_AD9/WKUP10)_13") (pintype "bidirectional"))
    )
    (net (code "70") (name "unconnected-(IC1-PA21(AFE0_AD1{slash}PIODCEN2)-Pad21)") (class "Default")
      (node (ref "IC1") (pin "21") (pinfunction "PA21(AFE0_AD1/PIODCEN2)_21") (pintype "bidirectional"))
    )
    (net (code "71") (name "unconnected-(IC1-PA22(PIODCCLK)-Pad26)") (class "Default")
      (node (ref "IC1") (pin "26") (pinfunction "PA22(PIODCCLK)_26") (pintype "bidirectional"))
    )
    (net (code "72") (name "unconnected-(IC1-PA23-Pad31)") (class "Default")
      (node (ref "IC1") (pin "31") (pinfunction "PA23_31") (pintype "bidirectional"))
    )
    (net (code "73") (name "unconnected-(IC1-PA24-Pad38)") (class "Default")
      (node (ref "IC1") (pin "38") (pinfunction "PA24_38") (pintype "bidirectional"))
    )
    (net (code "74") (name "unconnected-(IC1-PB3(AFE0_AD2{slash}WKUP12)-Pad20)") (class "Default")
      (node (ref "IC1") (pin "20") (pinfunction "PB3(AFE0_AD2/WKUP12)_20") (pintype "bidirectional"))
    )
    (net (code "75") (name "unconnected-(IC1-PB13(DAC0)-Pad100)") (class "Default")
      (node (ref "IC1") (pin "100") (pinfunction "PB13(DAC0)_100") (pintype "bidirectional"))
    )
    (net (code "76") (name "unconnected-(IC1-PD0(DAC1)-Pad1)") (class "Default")
      (node (ref "IC1") (pin "1") (pinfunction "PD0(DAC1)_1") (pintype "bidirectional"))
    )
    (net (code "77") (name "unconnected-(IC1-PD1-Pad92)") (class "Default")
      (node (ref "IC1") (pin "92") (pinfunction "PD1_92") (pintype "bidirectional"))
    )
    (net (code "78") (name "unconnected-(IC1-PD2-Pad91)") (class "Default")
      (node (ref "IC1") (pin "91") (pinfunction "PD2_91") (pintype "bidirectional"))
    )
    (net (code "79") (name "unconnected-(IC1-PD3-Pad89)") (class "Default")
      (node (ref "IC1") (pin "89") (pinfunction "PD3_89") (pintype "bidirectional"))
    )
    (net (code "80") (name "unconnected-(IC1-PD4-Pad88)") (class "Default")
      (node (ref "IC1") (pin "88") (pinfunction "PD4_88") (pintype "bidirectional"))
    )
    (net (code "81") (name "unconnected-(IC1-PD5-Pad87)") (class "Default")
      (node (ref "IC1") (pin "87") (pinfunction "PD5_87") (pintype "bidirectional"))
    )
    (net (code "82") (name "unconnected-(IC1-PD6-Pad85)") (class "Default")
      (node (ref "IC1") (pin "85") (pinfunction "PD6_85") (pintype "bidirectional"))
    )
    (net (code "83") (name "unconnected-(IC1-PD7-Pad84)") (class "Default")
      (node (ref "IC1") (pin "84") (pinfunction "PD7_84") (pintype "bidirectional"))
    )
    (net (code "84") (name "unconnected-(IC1-PD8-Pad80)") (class "Default")
      (node (ref "IC1") (pin "80") (pinfunction "PD8_80") (pintype "bidirectional"))
    )
    (net (code "85") (name "unconnected-(IC1-PD9-Pad78)") (class "Default")
      (node (ref "IC1") (pin "78") (pinfunction "PD9_78") (pintype "bidirectional"))
    )
    (net (code "86") (name "unconnected-(IC1-PD10-Pad71)") (class "Default")
      (node (ref "IC1") (pin "71") (pinfunction "PD10_71") (pintype "bidirectional"))
    )
    (net (code "87") (name "unconnected-(IC1-PD11-Pad69)") (class "Default")
      (node (ref "IC1") (pin "69") (pinfunction "PD11_69") (pintype "bidirectional"))
    )
    (net (code "88") (name "unconnected-(IC1-PD12-Pad65)") (class "Default")
      (node (ref "IC1") (pin "65") (pinfunction "PD12_65") (pintype "bidirectional"))
    )
    (net (code "89") (name "unconnected-(IC1-PD13-Pad62)") (class "Default")
      (node (ref "IC1") (pin "62") (pinfunction "PD13_62") (pintype "bidirectional"))
    )
    (net (code "90") (name "unconnected-(IC1-PD14-Pad59)") (class "Default")
      (node (ref "IC1") (pin "59") (pinfunction "PD14_59") (pintype "bidirectional"))
    )
    (net (code "91") (name "unconnected-(IC1-PD18-Pad49)") (class "Default")
      (node (ref "IC1") (pin "49") (pinfunction "PD18_49") (pintype "bidirectional"))
    )
    (net (code "92") (name "unconnected-(IC1-PD19-Pad47)") (class "Default")
      (node (ref "IC1") (pin "47") (pinfunction "PD19_47") (pintype "bidirectional"))
    )
    (net (code "93") (name "unconnected-(IC1-PD20-Pad45)") (class "Default")
      (node (ref "IC1") (pin "45") (pinfunction "PD20_45") (pintype "bidirectional"))
    )
    (net (code "94") (name "unconnected-(IC1-PD21-Pad43)") (class "Default")
      (node (ref "IC1") (pin "43") (pinfunction "PD21_43") (pintype "bidirectional"))
    )
    (net (code "95") (name "unconnected-(IC1-PD22-Pad41)") (class "Default")
      (node (ref "IC1") (pin "41") (pinfunction "PD22_41") (pintype "bidirectional"))
    )
    (net (code "96") (name "unconnected-(IC1-PD24-Pad37)") (class "Default")
      (node (ref "IC1") (pin "37") (pinfunction "PD24_37") (pintype "bidirectional"))
    )
    (net (code "97") (name "unconnected-(IC1-PD27-Pad32)") (class "Default")
      (node (ref "IC1") (pin "32") (pinfunction "PD27_32") (pintype "bidirectional"))
    )
    (net (code "98") (name "unconnected-(IC1-PD28(WKUP5)-Pad51)") (class "Default")
      (node (ref "IC1") (pin "51") (pinfunction "PD28(WKUP5)_51") (pintype "bidirectional"))
    )
    (net (code "99") (name "unconnected-(IC1-PD31-Pad2)") (class "Default")
      (node (ref "IC1") (pin "2") (pinfunction "PD31_2") (pintype "bidirectional"))
    )
    (net (code "100") (name "unconnected-(IC1-TST-Pad60)") (class "Default")
      (node (ref "IC1") (pin "60") (pinfunction "TST_60") (pintype "bidirectional"))
    )
    (net (code "101") (name "unconnected-(IC2-I0D-Pad14)") (class "Default")
      (node (ref "IC2") (pin "14") (pinfunction "I0D_14") (pintype "bidirectional"))
    )
    (net (code "102") (name "unconnected-(IC2-I1D-Pad13)") (class "Default")
      (node (ref "IC2") (pin "13") (pinfunction "I1D_13") (pintype "bidirectional"))
    )
    (net (code "103") (name "unconnected-(IC2-YD-Pad12)") (class "Default")
      (node (ref "IC2") (pin "12") (pinfunction "YD_12") (pintype "bidirectional"))
    )
    (net (code "104") (name "unconnected-(IC3-I0D-Pad14)") (class "Default")
      (node (ref "IC3") (pin "14") (pinfunction "I0D_14") (pintype "bidirectional"))
    )
    (net (code "105") (name "unconnected-(IC3-I1D-Pad13)") (class "Default")
      (node (ref "IC3") (pin "13") (pinfunction "I1D_13") (pintype "bidirectional"))
    )
    (net (code "106") (name "unconnected-(IC3-YD-Pad12)") (class "Default")
      (node (ref "IC3") (pin "12") (pinfunction "YD_12") (pintype "bidirectional"))
    )
    (net (code "107") (name "unconnected-(JP1-PadID)") (class "Default")
      (node (ref "JP1") (pin "ID") (pinfunction "ID_ID") (pintype "bidirectional"))
    )
    (net (code "108") (name "unconnected-(JP5-Pad7)") (class "Default")
      (node (ref "JP5") (pin "7") (pinfunction "7_7") (pintype "passive"))
    )
    (net (code "109") (name "unconnected-(JP5-Pad8)") (class "Default")
      (node (ref "JP5") (pin "8") (pinfunction "8_8") (pintype "passive"))
    )
    (net (code "110") (name "unconnected-(R7-Pad1)") (class "Default")
      (node (ref "R7") (pin "1") (pinfunction "1_1") (pintype "passive"))
    )
    (net (code "111") (name "unconnected-(R7-Pad7)") (class "Default")
      (node (ref "R7") (pin "7") (pinfunction "7_7") (pintype "passive"))
    )
    (net (code "112") (name "unconnected-(R7-Pad8)") (class "Default")
      (node (ref "R7") (pin "8") (pinfunction "8_8") (pintype "passive"))
    )
    (net (code "113") (name "unconnected-(R7-Pad9)") (class "Default")
      (node (ref "R7") (pin "9") (pinfunction "9_9") (pintype "passive"))
    )
    (net (code "114") (name "unconnected-(R7-Pad10)") (class "Default")
      (node (ref "R7") (pin "10") (pinfunction "10_10") (pintype "passive"))
    )
    (net (code "115") (name "~{A}{slash}B") (class "Default")
      (node (ref "IC1") (pin "53") (pinfunction "PD17_53") (pintype "bidirectional"))
      (node (ref "IC2") (pin "1") (pinfunction "S_1") (pintype "input"))
      (node (ref "IC3") (pin "1") (pinfunction "S_1") (pintype "input"))
    )
    (net (code "116") (name "~{CDA}") (class "Default")
      (node (ref "IC1") (pin "35") (pinfunction "PD25_35") (pintype "bidirectional"))
      (node (ref "JP3") (pin "CDA") (pinfunction "CDA_CDA") (pintype "bidirectional"))
    )
    (net (code "117") (name "~{CDB}") (class "Default")
      (node (ref "IC1") (pin "36") (pinfunction "PD26_36") (pintype "bidirectional"))
      (node (ref "JP4") (pin "CDB") (pinfunction "CDB_CDB") (pintype "bidirectional"))
    )
    (net (code "118") (name "~{CRDEN}") (class "Default")
      (node (ref "IC1") (pin "75") (pinfunction "PD15_75") (pintype "bidirectional"))
      (node (ref "IC2") (pin "15") (pinfunction "~{E}_15") (pintype "input"))
      (node (ref "IC3") (pin "15") (pinfunction "~{E}_15") (pintype "input"))
      (node (ref "R6") (pin "1") (pinfunction "1_1") (pintype "passive"))
    )
    (net (code "119") (name "~{CRDPWR}") (class "Default")
      (node (ref "IC1") (pin "56") (pinfunction "PD16_56") (pintype "bidirectional"))
      (node (ref "Q3") (pin "1") (pinfunction "G_1") (pintype "passive"))
      (node (ref "R5") (pin "1") (pinfunction "1_1") (pintype "passive"))
    )
    (net (code "120") (name "~{SW0}") (class "Default")
      (node (ref "IC1") (pin "23") (pinfunction "PD30(AFE0_AD0)_23") (pintype "bidirectional"))
      (node (ref "SW1") (pin "B") (pinfunction "S_B") (pintype "passive"))
      (node (ref "SW1") (pin "B'") (pinfunction "S1_B'") (pintype "passive"))
    )
  )
)
